# FAL6567e.net
KiCad netlist of a schematic drawn in EAGLE
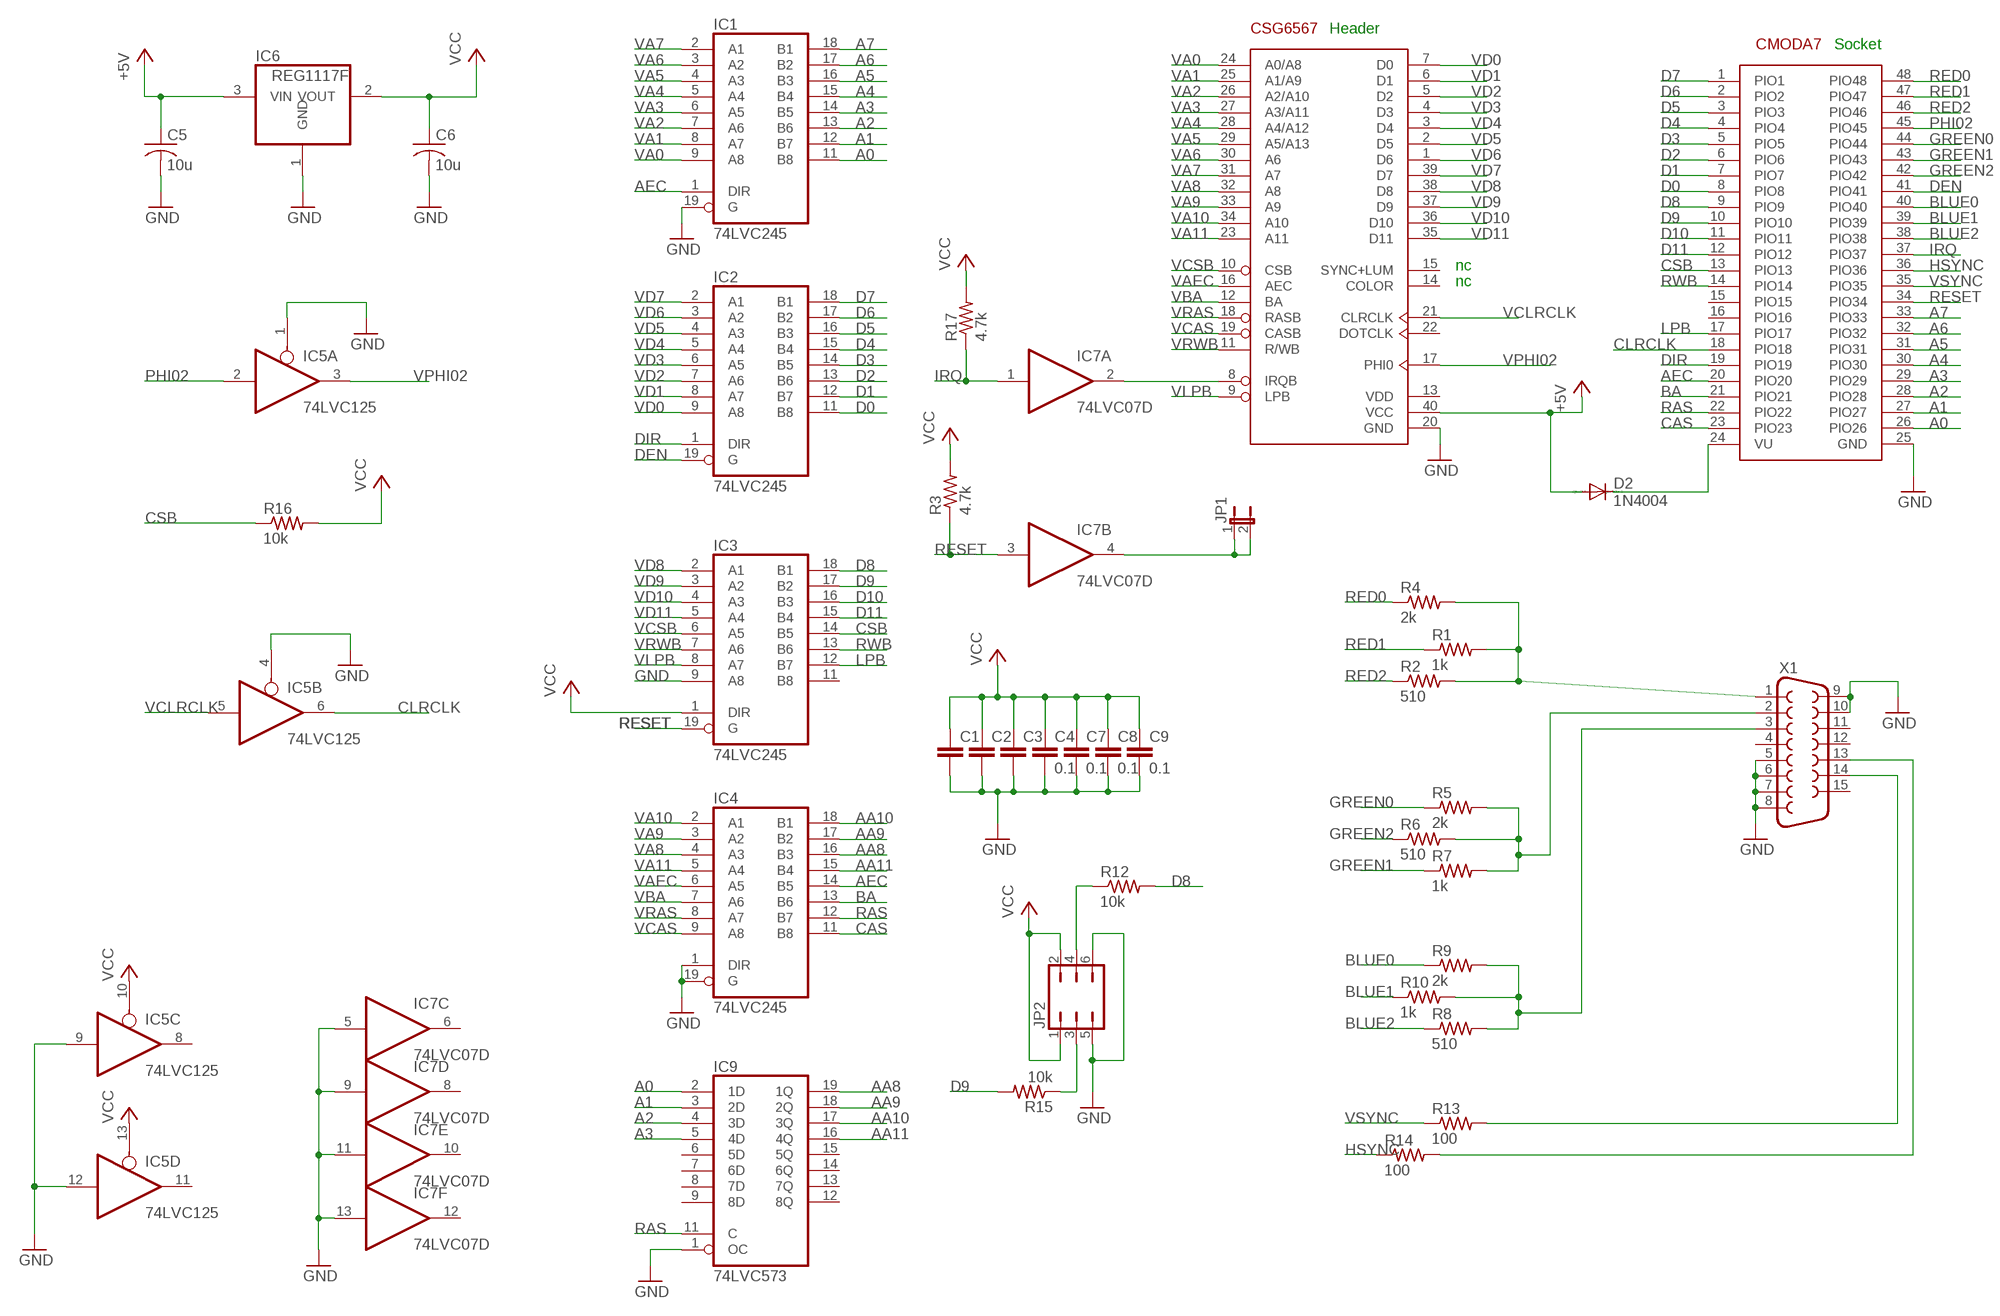
[diagram p0: schematic, sheet 1]

(export (version "E")
  (design (tool "Eeschema 10.0.6"))
  (components
    (comp (ref "C1")
      (value "C-EU050-024X044")
      (footprint "eagle-import:C050-024X044")
      (libsource (lib "eagle-import") (part "C-EU050-024X044"))
    )
    (comp (ref "C2")
      (value "C-EU050-024X044")
      (footprint "eagle-import:C050-024X044")
      (libsource (lib "eagle-import") (part "C-EU050-024X044"))
    )
    (comp (ref "C3")
      (value "C-EU050-024X044")
      (footprint "eagle-import:C050-024X044")
      (libsource (lib "eagle-import") (part "C-EU050-024X044"))
    )
    (comp (ref "C4")
      (value "0.1")
      (footprint "eagle-import:C050-024X044")
      (libsource (lib "eagle-import") (part "C-EU050-024X044"))
    )
    (comp (ref "C5")
      (value "10u")
      (footprint "eagle-import:C1206")
      (libsource (lib "eagle-import") (part "C-USC1206"))
    )
    (comp (ref "C6")
      (value "10u")
      (footprint "eagle-import:C1206")
      (libsource (lib "eagle-import") (part "C-USC1206"))
    )
    (comp (ref "C7")
      (value "0.1")
      (footprint "eagle-import:C050-024X044")
      (libsource (lib "eagle-import") (part "C-EU050-024X044"))
    )
    (comp (ref "C8")
      (value "0.1")
      (footprint "eagle-import:C050-024X044")
      (libsource (lib "eagle-import") (part "C-EU050-024X044"))
    )
    (comp (ref "C9")
      (value "0.1")
      (footprint "eagle-import:C050-024X044")
      (libsource (lib "eagle-import") (part "C-EU050-024X044"))
    )
    (comp (ref "D2")
      (value "1N4004")
      (footprint "eagle-import:DO41-10")
      (libsource (lib "eagle-import") (part "1N4004"))
    )
    (comp (ref "IC1")
      (value "74LVC245")
      (footprint "eagle-import:SO20W")
      (libsource (lib "eagle-import") (part "74245DWLS"))
    )
    (comp (ref "IC2")
      (value "74LVC245")
      (footprint "eagle-import:SO20W")
      (libsource (lib "eagle-import") (part "74245DWLS"))
    )
    (comp (ref "IC3")
      (value "74LVC245")
      (footprint "eagle-import:SO20W")
      (libsource (lib "eagle-import") (part "74245DWLS"))
    )
    (comp (ref "IC4")
      (value "74LVC245")
      (footprint "eagle-import:SO20W")
      (libsource (lib "eagle-import") (part "74245DWLS"))
    )
    (comp (ref "IC5")
      (value "74LVC125")
      (footprint "eagle-import:SO14")
      (libsource (lib "eagle-import") (part "74125LVC"))
    )
    (comp (ref "IC6")
      (value "REG1117F")
      (footprint "eagle-import:DD-3")
      (fields (field (name "MF") "TEXAS INSTRUMENTS") (field (name "MPN") "REG1117FAKTTT"))
      (libsource (lib "eagle-import") (part "REG1117F"))
    )
    (comp (ref "IC7")
      (value "74LVC07D")
      (footprint "eagle-import:SO14")
      (libsource (lib "eagle-import") (part "7407DLS"))
    )
    (comp (ref "IC9")
      (value "74LVC573")
      (footprint "eagle-import:SO20W")
      (libsource (lib "eagle-import") (part "74573LVC"))
    )
    (comp (ref "JP1")
      (value "JP1E")
      (footprint "eagle-import:JP1")
      (libsource (lib "eagle-import") (part "JP1E"))
    )
    (comp (ref "JP2")
      (value "JP3Q")
      (footprint "eagle-import:JP3Q")
      (libsource (lib "eagle-import") (part "JP3Q"))
    )
    (comp (ref "R1")
      (value "1k")
      (footprint "eagle-import:0204_7")
      (libsource (lib "eagle-import") (part "R-US_0204/7"))
    )
    (comp (ref "R2")
      (value "510")
      (footprint "eagle-import:0204_7")
      (libsource (lib "eagle-import") (part "R-US_0204/7"))
    )
    (comp (ref "R3")
      (value "4.7k")
      (footprint "eagle-import:0204_7")
      (libsource (lib "eagle-import") (part "R-US_0204/7"))
    )
    (comp (ref "R4")
      (value "2k")
      (footprint "eagle-import:0204_7")
      (libsource (lib "eagle-import") (part "R-US_0204/7"))
    )
    (comp (ref "R5")
      (value "2k")
      (footprint "eagle-import:0204_7")
      (libsource (lib "eagle-import") (part "R-US_0204/7"))
    )
    (comp (ref "R6")
      (value "510")
      (footprint "eagle-import:0204_7")
      (libsource (lib "eagle-import") (part "R-US_0204/7"))
    )
    (comp (ref "R7")
      (value "1k")
      (footprint "eagle-import:0204_7")
      (libsource (lib "eagle-import") (part "R-US_0204/7"))
    )
    (comp (ref "R8")
      (value "510")
      (footprint "eagle-import:0204_7")
      (libsource (lib "eagle-import") (part "R-US_0204/7"))
    )
    (comp (ref "R9")
      (value "2k")
      (footprint "eagle-import:0204_7")
      (libsource (lib "eagle-import") (part "R-US_0204/7"))
    )
    (comp (ref "R10")
      (value "1k")
      (footprint "eagle-import:0204_7")
      (libsource (lib "eagle-import") (part "R-US_0204/7"))
    )
    (comp (ref "R12")
      (value "10k")
      (footprint "eagle-import:0204_7")
      (libsource (lib "eagle-import") (part "R-US_0204/7"))
    )
    (comp (ref "R13")
      (value "100")
      (footprint "eagle-import:0204_7")
      (libsource (lib "eagle-import") (part "R-US_0204/7"))
    )
    (comp (ref "R14")
      (value "100")
      (footprint "eagle-import:0204_7")
      (libsource (lib "eagle-import") (part "R-US_0204/7"))
    )
    (comp (ref "R15")
      (value "10k")
      (footprint "eagle-import:0204_7")
      (libsource (lib "eagle-import") (part "R-US_0204/7"))
    )
    (comp (ref "R16")
      (value "10k")
      (footprint "eagle-import:0204_7")
      (libsource (lib "eagle-import") (part "R-US_0204/7"))
    )
    (comp (ref "R17")
      (value "4.7k")
      (footprint "eagle-import:0204_7")
      (libsource (lib "eagle-import") (part "R-US_0204/7"))
    )
    (comp (ref "U$1")
      (value "CSG6567")
      (footprint "eagle-import:DIP-40")
      (libsource (lib "eagle-import") (part "CSG6567"))
    )
    (comp (ref "U$2")
      (value "CMODA7")
      (footprint "eagle-import:DIL48")
      (libsource (lib "eagle-import") (part "CMODA7"))
    )
    (comp (ref "X1")
      (value "F15HDV")
      (footprint "eagle-import:HDF15V")
      (libsource (lib "eagle-import") (part "F15HDV"))
    )
  )
  (nets
    (net (code "1") (name "+5V") (class "Default")
      (node (ref "C5") (pin "1") (pinfunction "1_1") (pintype "passive"))
      (node (ref "D2") (pin "A") (pinfunction "A_A") (pintype "passive"))
      (node (ref "IC6") (pin "3") (pinfunction "VIN_3") (pintype "input"))
      (node (ref "U$1") (pin "40") (pinfunction "VCC_40") (pintype "power_in"))
    )
    (net (code "2") (name "/A0") (class "Default")
      (node (ref "IC1") (pin "11") (pinfunction "B8_11") (pintype "bidirectional"))
      (node (ref "IC9") (pin "2") (pinfunction "1D_2") (pintype "input"))
      (node (ref "U$2") (pin "26") (pinfunction "PIO26_26") (pintype "bidirectional"))
    )
    (net (code "3") (name "/A1") (class "Default")
      (node (ref "IC1") (pin "12") (pinfunction "B7_12") (pintype "bidirectional"))
      (node (ref "IC9") (pin "3") (pinfunction "2D_3") (pintype "input"))
      (node (ref "U$2") (pin "27") (pinfunction "PIO27_27") (pintype "bidirectional"))
    )
    (net (code "4") (name "/A2") (class "Default")
      (node (ref "IC1") (pin "13") (pinfunction "B6_13") (pintype "bidirectional"))
      (node (ref "IC9") (pin "4") (pinfunction "3D_4") (pintype "input"))
      (node (ref "U$2") (pin "28") (pinfunction "PIO28_28") (pintype "bidirectional"))
    )
    (net (code "5") (name "/A3") (class "Default")
      (node (ref "IC1") (pin "14") (pinfunction "B5_14") (pintype "bidirectional"))
      (node (ref "IC9") (pin "5") (pinfunction "4D_5") (pintype "input"))
      (node (ref "U$2") (pin "29") (pinfunction "PIO29_29") (pintype "bidirectional"))
    )
    (net (code "6") (name "/A4") (class "Default")
      (node (ref "IC1") (pin "15") (pinfunction "B4_15") (pintype "bidirectional"))
      (node (ref "U$2") (pin "30") (pinfunction "PIO30_30") (pintype "bidirectional"))
    )
    (net (code "7") (name "/A5") (class "Default")
      (node (ref "IC1") (pin "16") (pinfunction "B3_16") (pintype "bidirectional"))
      (node (ref "U$2") (pin "31") (pinfunction "PIO31_31") (pintype "bidirectional"))
    )
    (net (code "8") (name "/A6") (class "Default")
      (node (ref "IC1") (pin "17") (pinfunction "B2_17") (pintype "bidirectional"))
      (node (ref "U$2") (pin "32") (pinfunction "PIO32_32") (pintype "bidirectional"))
    )
    (net (code "9") (name "/A7") (class "Default")
      (node (ref "IC1") (pin "18") (pinfunction "B1_18") (pintype "bidirectional"))
      (node (ref "U$2") (pin "33") (pinfunction "PIO33_33") (pintype "bidirectional"))
    )
    (net (code "10") (name "/AA8") (class "Default")
      (node (ref "IC4") (pin "16") (pinfunction "B3_16") (pintype "bidirectional"))
      (node (ref "IC9") (pin "19") (pinfunction "1Q_19") (pintype "tri_state"))
    )
    (net (code "11") (name "/AA9") (class "Default")
      (node (ref "IC4") (pin "17") (pinfunction "B2_17") (pintype "bidirectional"))
      (node (ref "IC9") (pin "18") (pinfunction "2Q_18") (pintype "tri_state"))
    )
    (net (code "12") (name "/AA10") (class "Default")
      (node (ref "IC4") (pin "18") (pinfunction "B1_18") (pintype "bidirectional"))
      (node (ref "IC9") (pin "17") (pinfunction "3Q_17") (pintype "tri_state"))
    )
    (net (code "13") (name "/AA11") (class "Default")
      (node (ref "IC4") (pin "15") (pinfunction "B4_15") (pintype "bidirectional"))
      (node (ref "IC9") (pin "16") (pinfunction "4Q_16") (pintype "tri_state"))
    )
    (net (code "14") (name "/AEC") (class "Default")
      (node (ref "IC1") (pin "1") (pinfunction "DIR_1") (pintype "input"))
      (node (ref "IC4") (pin "14") (pinfunction "B5_14") (pintype "bidirectional"))
      (node (ref "U$2") (pin "20") (pinfunction "PIO20_20") (pintype "bidirectional"))
    )
    (net (code "15") (name "/BA") (class "Default")
      (node (ref "IC4") (pin "13") (pinfunction "B6_13") (pintype "bidirectional"))
      (node (ref "U$2") (pin "21") (pinfunction "PIO21_21") (pintype "bidirectional"))
    )
    (net (code "16") (name "/BLUE0") (class "Default")
      (node (ref "R9") (pin "1") (pinfunction "1_1") (pintype "passive"))
      (node (ref "U$2") (pin "40") (pinfunction "PIO40_40") (pintype "bidirectional"))
    )
    (net (code "17") (name "/BLUE1") (class "Default")
      (node (ref "R10") (pin "1") (pinfunction "1_1") (pintype "passive"))
      (node (ref "U$2") (pin "39") (pinfunction "PIO39_39") (pintype "bidirectional"))
    )
    (net (code "18") (name "/BLUE2") (class "Default")
      (node (ref "R8") (pin "1") (pinfunction "1_1") (pintype "passive"))
      (node (ref "U$2") (pin "38") (pinfunction "PIO38_38") (pintype "bidirectional"))
    )
    (net (code "19") (name "/CAS") (class "Default")
      (node (ref "IC4") (pin "11") (pinfunction "B8_11") (pintype "bidirectional"))
      (node (ref "U$2") (pin "23") (pinfunction "PIO23_23") (pintype "bidirectional"))
    )
    (net (code "20") (name "/CLRCLK") (class "Default")
      (node (ref "IC5") (pin "6") (pinfunction "O_6") (pintype "tri_state"))
      (node (ref "U$2") (pin "18") (pinfunction "PIO18_18") (pintype "bidirectional"))
    )
    (net (code "21") (name "/CSB") (class "Default")
      (node (ref "IC3") (pin "14") (pinfunction "B5_14") (pintype "bidirectional"))
      (node (ref "R16") (pin "1") (pinfunction "1_1") (pintype "passive"))
      (node (ref "U$2") (pin "13") (pinfunction "PIO13_13") (pintype "bidirectional"))
    )
    (net (code "22") (name "/D0") (class "Default")
      (node (ref "IC2") (pin "11") (pinfunction "B8_11") (pintype "bidirectional"))
      (node (ref "U$2") (pin "8") (pinfunction "PIO8_8") (pintype "bidirectional"))
    )
    (net (code "23") (name "/D1") (class "Default")
      (node (ref "IC2") (pin "12") (pinfunction "B7_12") (pintype "bidirectional"))
      (node (ref "U$2") (pin "7") (pinfunction "PIO7_7") (pintype "bidirectional"))
    )
    (net (code "24") (name "/D2") (class "Default")
      (node (ref "IC2") (pin "13") (pinfunction "B6_13") (pintype "bidirectional"))
      (node (ref "U$2") (pin "6") (pinfunction "PIO6_6") (pintype "bidirectional"))
    )
    (net (code "25") (name "/D3") (class "Default")
      (node (ref "IC2") (pin "14") (pinfunction "B5_14") (pintype "bidirectional"))
      (node (ref "U$2") (pin "5") (pinfunction "PIO5_5") (pintype "bidirectional"))
    )
    (net (code "26") (name "/D4") (class "Default")
      (node (ref "IC2") (pin "15") (pinfunction "B4_15") (pintype "bidirectional"))
      (node (ref "U$2") (pin "4") (pinfunction "PIO4_4") (pintype "bidirectional"))
    )
    (net (code "27") (name "/D5") (class "Default")
      (node (ref "IC2") (pin "16") (pinfunction "B3_16") (pintype "bidirectional"))
      (node (ref "U$2") (pin "3") (pinfunction "PIO3_3") (pintype "bidirectional"))
    )
    (net (code "28") (name "/D6") (class "Default")
      (node (ref "IC2") (pin "17") (pinfunction "B2_17") (pintype "bidirectional"))
      (node (ref "U$2") (pin "2") (pinfunction "PIO2_2") (pintype "bidirectional"))
    )
    (net (code "29") (name "/D7") (class "Default")
      (node (ref "IC2") (pin "18") (pinfunction "B1_18") (pintype "bidirectional"))
      (node (ref "U$2") (pin "1") (pinfunction "PIO1_1") (pintype "bidirectional"))
    )
    (net (code "30") (name "/D8") (class "Default")
      (node (ref "IC3") (pin "18") (pinfunction "B1_18") (pintype "bidirectional"))
      (node (ref "R12") (pin "2") (pinfunction "2_2") (pintype "passive"))
      (node (ref "U$2") (pin "9") (pinfunction "PIO9_9") (pintype "bidirectional"))
    )
    (net (code "31") (name "/D9") (class "Default")
      (node (ref "IC3") (pin "17") (pinfunction "B2_17") (pintype "bidirectional"))
      (node (ref "R15") (pin "2") (pinfunction "2_2") (pintype "passive"))
      (node (ref "U$2") (pin "10") (pinfunction "PIO10_10") (pintype "bidirectional"))
    )
    (net (code "32") (name "/D10") (class "Default")
      (node (ref "IC3") (pin "16") (pinfunction "B3_16") (pintype "bidirectional"))
      (node (ref "U$2") (pin "11") (pinfunction "PIO11_11") (pintype "bidirectional"))
    )
    (net (code "33") (name "/D11") (class "Default")
      (node (ref "IC3") (pin "15") (pinfunction "B4_15") (pintype "bidirectional"))
      (node (ref "U$2") (pin "12") (pinfunction "PIO12_12") (pintype "bidirectional"))
    )
    (net (code "34") (name "/DEN") (class "Default")
      (node (ref "IC2") (pin "19") (pinfunction "G_19") (pintype "input"))
      (node (ref "U$2") (pin "41") (pinfunction "PIO41_41") (pintype "bidirectional"))
    )
    (net (code "35") (name "/DIR") (class "Default")
      (node (ref "IC2") (pin "1") (pinfunction "DIR_1") (pintype "input"))
      (node (ref "U$2") (pin "19") (pinfunction "PIO19_19") (pintype "bidirectional"))
    )
    (net (code "36") (name "/GREEN0") (class "Default")
      (node (ref "R5") (pin "1") (pinfunction "1_1") (pintype "passive"))
      (node (ref "U$2") (pin "44") (pinfunction "PIO44_44") (pintype "bidirectional"))
    )
    (net (code "37") (name "/GREEN1") (class "Default")
      (node (ref "R7") (pin "1") (pinfunction "1_1") (pintype "passive"))
      (node (ref "U$2") (pin "43") (pinfunction "PIO43_43") (pintype "bidirectional"))
    )
    (net (code "38") (name "/GREEN2") (class "Default")
      (node (ref "R6") (pin "1") (pinfunction "1_1") (pintype "passive"))
      (node (ref "U$2") (pin "42") (pinfunction "PIO42_42") (pintype "bidirectional"))
    )
    (net (code "39") (name "/HSYNC") (class "Default")
      (node (ref "R14") (pin "1") (pinfunction "1_1") (pintype "passive"))
      (node (ref "U$2") (pin "36") (pinfunction "PIO36_36") (pintype "bidirectional"))
    )
    (net (code "40") (name "/IRQ") (class "Default")
      (node (ref "IC7") (pin "1") (pinfunction "I_1") (pintype "input"))
      (node (ref "R17") (pin "1") (pinfunction "1_1") (pintype "passive"))
      (node (ref "U$2") (pin "37") (pinfunction "PIO37_37") (pintype "bidirectional"))
    )
    (net (code "41") (name "/LPB") (class "Default")
      (node (ref "IC3") (pin "12") (pinfunction "B7_12") (pintype "bidirectional"))
      (node (ref "U$2") (pin "17") (pinfunction "PIO17_17") (pintype "bidirectional"))
    )
    (net (code "42") (name "/PHI02") (class "Default")
      (node (ref "IC5") (pin "2") (pinfunction "I_2") (pintype "input"))
      (node (ref "U$2") (pin "45") (pinfunction "PIO45_45") (pintype "bidirectional"))
    )
    (net (code "43") (name "/RAS") (class "Default")
      (node (ref "IC4") (pin "12") (pinfunction "B7_12") (pintype "bidirectional"))
      (node (ref "IC9") (pin "11") (pinfunction "C_11") (pintype "input"))
      (node (ref "U$2") (pin "22") (pinfunction "PIO22_22") (pintype "bidirectional"))
    )
    (net (code "44") (name "/RED0") (class "Default")
      (node (ref "R4") (pin "1") (pinfunction "1_1") (pintype "passive"))
      (node (ref "U$2") (pin "48") (pinfunction "PIO48_48") (pintype "bidirectional"))
    )
    (net (code "45") (name "/RED1") (class "Default")
      (node (ref "R1") (pin "1") (pinfunction "1_1") (pintype "passive"))
      (node (ref "U$2") (pin "47") (pinfunction "PIO47_47") (pintype "bidirectional"))
    )
    (net (code "46") (name "/RED2") (class "Default")
      (node (ref "R2") (pin "1") (pinfunction "1_1") (pintype "passive"))
      (node (ref "U$2") (pin "46") (pinfunction "PIO46_46") (pintype "bidirectional"))
    )
    (net (code "47") (name "/RESET") (class "Default")
      (node (ref "IC3") (pin "19") (pinfunction "G_19") (pintype "input"))
      (node (ref "IC7") (pin "3") (pinfunction "I_3") (pintype "input"))
      (node (ref "R3") (pin "1") (pinfunction "1_1") (pintype "passive"))
      (node (ref "U$2") (pin "34") (pinfunction "PIO34_34") (pintype "bidirectional"))
    )
    (net (code "48") (name "/RWB") (class "Default")
      (node (ref "IC3") (pin "13") (pinfunction "B6_13") (pintype "bidirectional"))
      (node (ref "U$2") (pin "14") (pinfunction "PIO14_14") (pintype "bidirectional"))
    )
    (net (code "49") (name "/VA0") (class "Default")
      (node (ref "IC1") (pin "9") (pinfunction "A8_9") (pintype "bidirectional"))
      (node (ref "U$1") (pin "24") (pinfunction "A0/A8_24") (pintype "bidirectional"))
    )
    (net (code "50") (name "/VA1") (class "Default")
      (node (ref "IC1") (pin "8") (pinfunction "A7_8") (pintype "bidirectional"))
      (node (ref "U$1") (pin "25") (pinfunction "A1/A9_25") (pintype "bidirectional"))
    )
    (net (code "51") (name "/VA2") (class "Default")
      (node (ref "IC1") (pin "7") (pinfunction "A6_7") (pintype "bidirectional"))
      (node (ref "U$1") (pin "26") (pinfunction "A2/A10_26") (pintype "bidirectional"))
    )
    (net (code "52") (name "/VA3") (class "Default")
      (node (ref "IC1") (pin "6") (pinfunction "A5_6") (pintype "bidirectional"))
      (node (ref "U$1") (pin "27") (pinfunction "A3/A11_27") (pintype "bidirectional"))
    )
    (net (code "53") (name "/VA4") (class "Default")
      (node (ref "IC1") (pin "5") (pinfunction "A4_5") (pintype "bidirectional"))
      (node (ref "U$1") (pin "28") (pinfunction "A4/A12_28") (pintype "bidirectional"))
    )
    (net (code "54") (name "/VA5") (class "Default")
      (node (ref "IC1") (pin "4") (pinfunction "A3_4") (pintype "bidirectional"))
      (node (ref "U$1") (pin "29") (pinfunction "A5/A13_29") (pintype "bidirectional"))
    )
    (net (code "55") (name "/VA6") (class "Default")
      (node (ref "IC1") (pin "3") (pinfunction "A2_3") (pintype "bidirectional"))
      (node (ref "U$1") (pin "30") (pinfunction "A6_30") (pintype "bidirectional"))
    )
    (net (code "56") (name "/VA7") (class "Default")
      (node (ref "IC1") (pin "2") (pinfunction "A1_2") (pintype "bidirectional"))
      (node (ref "U$1") (pin "31") (pinfunction "A7_31") (pintype "bidirectional"))
    )
    (net (code "57") (name "/VA8") (class "Default")
      (node (ref "IC4") (pin "4") (pinfunction "A3_4") (pintype "bidirectional"))
      (node (ref "U$1") (pin "32") (pinfunction "A8_32") (pintype "output"))
    )
    (net (code "58") (name "/VA9") (class "Default")
      (node (ref "IC4") (pin "3") (pinfunction "A2_3") (pintype "bidirectional"))
      (node (ref "U$1") (pin "33") (pinfunction "A9_33") (pintype "output"))
    )
    (net (code "59") (name "/VA10") (class "Default")
      (node (ref "IC4") (pin "2") (pinfunction "A1_2") (pintype "bidirectional"))
      (node (ref "U$1") (pin "34") (pinfunction "A10_34") (pintype "output"))
    )
    (net (code "60") (name "/VA11") (class "Default")
      (node (ref "IC4") (pin "5") (pinfunction "A4_5") (pintype "bidirectional"))
      (node (ref "U$1") (pin "23") (pinfunction "A11_23") (pintype "output"))
    )
    (net (code "61") (name "/VAEC") (class "Default")
      (node (ref "IC4") (pin "6") (pinfunction "A5_6") (pintype "bidirectional"))
      (node (ref "U$1") (pin "16") (pinfunction "AEC_16") (pintype "output"))
    )
    (net (code "62") (name "/VBA") (class "Default")
      (node (ref "IC4") (pin "7") (pinfunction "A6_7") (pintype "bidirectional"))
      (node (ref "U$1") (pin "12") (pinfunction "BA_12") (pintype "output"))
    )
    (net (code "63") (name "/VCAS") (class "Default")
      (node (ref "IC4") (pin "9") (pinfunction "A8_9") (pintype "bidirectional"))
      (node (ref "U$1") (pin "19") (pinfunction "CASB_19") (pintype "output"))
    )
    (net (code "64") (name "/VCLRCLK") (class "Default")
      (node (ref "IC5") (pin "5") (pinfunction "I_5") (pintype "input"))
      (node (ref "U$1") (pin "21") (pinfunction "CLRCLK_21") (pintype "input"))
    )
    (net (code "65") (name "/VCSB") (class "Default")
      (node (ref "IC3") (pin "6") (pinfunction "A5_6") (pintype "bidirectional"))
      (node (ref "U$1") (pin "10") (pinfunction "CSB_10") (pintype "input"))
    )
    (net (code "66") (name "/VD0") (class "Default")
      (node (ref "IC2") (pin "9") (pinfunction "A8_9") (pintype "bidirectional"))
      (node (ref "U$1") (pin "7") (pinfunction "D0_7") (pintype "bidirectional"))
    )
    (net (code "67") (name "/VD1") (class "Default")
      (node (ref "IC2") (pin "8") (pinfunction "A7_8") (pintype "bidirectional"))
      (node (ref "U$1") (pin "6") (pinfunction "D1_6") (pintype "bidirectional"))
    )
    (net (code "68") (name "/VD2") (class "Default")
      (node (ref "IC2") (pin "7") (pinfunction "A6_7") (pintype "bidirectional"))
      (node (ref "U$1") (pin "5") (pinfunction "D2_5") (pintype "bidirectional"))
    )
    (net (code "69") (name "/VD3") (class "Default")
      (node (ref "IC2") (pin "6") (pinfunction "A5_6") (pintype "bidirectional"))
      (node (ref "U$1") (pin "4") (pinfunction "D3_4") (pintype "bidirectional"))
    )
    (net (code "70") (name "/VD4") (class "Default")
      (node (ref "IC2") (pin "5") (pinfunction "A4_5") (pintype "bidirectional"))
      (node (ref "U$1") (pin "3") (pinfunction "D4_3") (pintype "bidirectional"))
    )
    (net (code "71") (name "/VD5") (class "Default")
      (node (ref "IC2") (pin "4") (pinfunction "A3_4") (pintype "bidirectional"))
      (node (ref "U$1") (pin "2") (pinfunction "D5_2") (pintype "bidirectional"))
    )
    (net (code "72") (name "/VD6") (class "Default")
      (node (ref "IC2") (pin "3") (pinfunction "A2_3") (pintype "bidirectional"))
      (node (ref "U$1") (pin "1") (pinfunction "D6_1") (pintype "bidirectional"))
    )
    (net (code "73") (name "/VD7") (class "Default")
      (node (ref "IC2") (pin "2") (pinfunction "A1_2") (pintype "bidirectional"))
      (node (ref "U$1") (pin "39") (pinfunction "D7_39") (pintype "bidirectional"))
    )
    (net (code "74") (name "/VD8") (class "Default")
      (node (ref "IC3") (pin "2") (pinfunction "A1_2") (pintype "bidirectional"))
      (node (ref "U$1") (pin "38") (pinfunction "D8_38") (pintype "input"))
    )
    (net (code "75") (name "/VD9") (class "Default")
      (node (ref "IC3") (pin "3") (pinfunction "A2_3") (pintype "bidirectional"))
      (node (ref "U$1") (pin "37") (pinfunction "D9_37") (pintype "input"))
    )
    (net (code "76") (name "/VD10") (class "Default")
      (node (ref "IC3") (pin "4") (pinfunction "A3_4") (pintype "bidirectional"))
      (node (ref "U$1") (pin "36") (pinfunction "D10_36") (pintype "input"))
    )
    (net (code "77") (name "/VD11") (class "Default")
      (node (ref "IC3") (pin "5") (pinfunction "A4_5") (pintype "bidirectional"))
      (node (ref "U$1") (pin "35") (pinfunction "D11_35") (pintype "input"))
    )
    (net (code "78") (name "/VDD") (class "Default")
      (node (ref "U$1") (pin "13") (pinfunction "VDD_13") (pintype "power_in"))
    )
    (net (code "79") (name "/VLPB") (class "Default")
      (node (ref "IC3") (pin "8") (pinfunction "A7_8") (pintype "bidirectional"))
      (node (ref "U$1") (pin "9") (pinfunction "LPB_9") (pintype "input"))
    )
    (net (code "80") (name "/VPHI02") (class "Default")
      (node (ref "IC5") (pin "3") (pinfunction "O_3") (pintype "tri_state"))
      (node (ref "U$1") (pin "17") (pinfunction "PHI0_17") (pintype "output"))
    )
    (net (code "81") (name "/VRAS") (class "Default")
      (node (ref "IC4") (pin "8") (pinfunction "A7_8") (pintype "bidirectional"))
      (node (ref "U$1") (pin "18") (pinfunction "RASB_18") (pintype "output"))
    )
    (net (code "82") (name "/VRWB") (class "Default")
      (node (ref "IC3") (pin "7") (pinfunction "A6_7") (pintype "bidirectional"))
      (node (ref "U$1") (pin "11") (pinfunction "R/WB_11") (pintype "input"))
    )
    (net (code "83") (name "/VSYNC") (class "Default")
      (node (ref "R13") (pin "1") (pinfunction "1_1") (pintype "passive"))
      (node (ref "U$2") (pin "35") (pinfunction "PIO35_35") (pintype "bidirectional"))
    )
    (net (code "84") (name "GND") (class "Default")
      (node (ref "C1") (pin "2") (pinfunction "2_2") (pintype "passive"))
      (node (ref "C2") (pin "2") (pinfunction "2_2") (pintype "passive"))
      (node (ref "C3") (pin "2") (pinfunction "2_2") (pintype "passive"))
      (node (ref "C4") (pin "2") (pinfunction "2_2") (pintype "passive"))
      (node (ref "C5") (pin "2") (pinfunction "2_2") (pintype "passive"))
      (node (ref "C6") (pin "2") (pinfunction "2_2") (pintype "passive"))
      (node (ref "C7") (pin "2") (pinfunction "2_2") (pintype "passive"))
      (node (ref "C8") (pin "2") (pinfunction "2_2") (pintype "passive"))
      (node (ref "C9") (pin "2") (pinfunction "2_2") (pintype "passive"))
      (node (ref "IC1") (pin "19") (pinfunction "G_19") (pintype "input"))
      (node (ref "IC3") (pin "9") (pinfunction "A8_9") (pintype "bidirectional"))
      (node (ref "IC4") (pin "1") (pinfunction "DIR_1") (pintype "input"))
      (node (ref "IC4") (pin "19") (pinfunction "G_19") (pintype "input"))
      (node (ref "IC5") (pin "1") (pinfunction "OE_1") (pintype "input"))
      (node (ref "IC5") (pin "12") (pinfunction "I_12") (pintype "input"))
      (node (ref "IC5") (pin "4") (pinfunction "OE_4") (pintype "input"))
      (node (ref "IC5") (pin "9") (pinfunction "I_9") (pintype "input"))
      (node (ref "IC6") (pin "1") (pinfunction "GND_1") (pintype "power_in"))
      (node (ref "IC7") (pin "11") (pinfunction "I_11") (pintype "input"))
      (node (ref "IC7") (pin "13") (pinfunction "I_13") (pintype "input"))
      (node (ref "IC7") (pin "5") (pinfunction "I_5") (pintype "input"))
      (node (ref "IC7") (pin "9") (pinfunction "I_9") (pintype "input"))
      (node (ref "IC9") (pin "1") (pinfunction "OC_1") (pintype "input"))
      (node (ref "JP2") (pin "5") (pinfunction "5_5") (pintype "passive"))
      (node (ref "JP2") (pin "6") (pinfunction "6_6") (pintype "passive"))
      (node (ref "U$1") (pin "20") (pinfunction "GND_20") (pintype "power_in"))
      (node (ref "U$2") (pin "25") (pinfunction "GND_25") (pintype "power_in"))
      (node (ref "X1") (pin "10") (pinfunction "10_10") (pintype "passive"))
      (node (ref "X1") (pin "5") (pinfunction "5_5") (pintype "passive"))
      (node (ref "X1") (pin "6") (pinfunction "6_6") (pintype "passive"))
      (node (ref "X1") (pin "7") (pinfunction "7_7") (pintype "passive"))
      (node (ref "X1") (pin "8") (pinfunction "8_8") (pintype "passive"))
      (node (ref "X1") (pin "9") (pinfunction "9_9") (pintype "passive"))
    )
    (net (code "85") (name "Net-(IC7A-O)") (class "Default")
      (node (ref "IC7") (pin "2") (pinfunction "O_2") (pintype "open_collector"))
      (node (ref "U$1") (pin "8") (pinfunction "IRQB_8") (pintype "open_collector"))
    )
    (net (code "86") (name "Net-(IC7B-O)") (class "Default")
      (node (ref "IC7") (pin "4") (pinfunction "O_4") (pintype "open_collector"))
      (node (ref "JP1") (pin "1") (pinfunction "1_1") (pintype "passive"))
      (node (ref "JP1") (pin "2") (pinfunction "2_2") (pintype "passive"))
    )
    (net (code "87") (name "Net-(JP2-Pad3)") (class "Default")
      (node (ref "JP2") (pin "3") (pinfunction "3_3") (pintype "passive"))
      (node (ref "R15") (pin "1") (pinfunction "1_1") (pintype "passive"))
    )
    (net (code "88") (name "Net-(JP2-Pad4)") (class "Default")
      (node (ref "JP2") (pin "4") (pinfunction "4_4") (pintype "passive"))
      (node (ref "R12") (pin "1") (pinfunction "1_1") (pintype "passive"))
    )
    (net (code "89") (name "Net-(R1-Pad2)") (class "Default")
      (node (ref "R1") (pin "2") (pinfunction "2_2") (pintype "passive"))
      (node (ref "R2") (pin "2") (pinfunction "2_2") (pintype "passive"))
      (node (ref "R4") (pin "2") (pinfunction "2_2") (pintype "passive"))
      (node (ref "X1") (pin "1") (pinfunction "1_1") (pintype "passive"))
    )
    (net (code "90") (name "Net-(R5-Pad2)") (class "Default")
      (node (ref "R5") (pin "2") (pinfunction "2_2") (pintype "passive"))
      (node (ref "R6") (pin "2") (pinfunction "2_2") (pintype "passive"))
      (node (ref "R7") (pin "2") (pinfunction "2_2") (pintype "passive"))
      (node (ref "X1") (pin "2") (pinfunction "2_2") (pintype "passive"))
    )
    (net (code "91") (name "Net-(R10-Pad2)") (class "Default")
      (node (ref "R10") (pin "2") (pinfunction "2_2") (pintype "passive"))
      (node (ref "R8") (pin "2") (pinfunction "2_2") (pintype "passive"))
      (node (ref "R9") (pin "2") (pinfunction "2_2") (pintype "passive"))
      (node (ref "X1") (pin "3") (pinfunction "3_3") (pintype "passive"))
    )
    (net (code "92") (name "Net-(R13-Pad2)") (class "Default")
      (node (ref "R13") (pin "2") (pinfunction "2_2") (pintype "passive"))
      (node (ref "X1") (pin "14") (pinfunction "14_14") (pintype "passive"))
    )
    (net (code "93") (name "Net-(R14-Pad2)") (class "Default")
      (node (ref "R14") (pin "2") (pinfunction "2_2") (pintype "passive"))
      (node (ref "X1") (pin "13") (pinfunction "13_13") (pintype "passive"))
    )
    (net (code "94") (name "Net-(U$2-VU)") (class "Default")
      (node (ref "D2") (pin "C") (pinfunction "C_C") (pintype "passive"))
      (node (ref "U$2") (pin "24") (pinfunction "VU_24") (pintype "power_in"))
    )
    (net (code "95") (name "VCC") (class "Default")
      (node (ref "C1") (pin "1") (pinfunction "1_1") (pintype "passive"))
      (node (ref "C2") (pin "1") (pinfunction "1_1") (pintype "passive"))
      (node (ref "C3") (pin "1") (pinfunction "1_1") (pintype "passive"))
      (node (ref "C4") (pin "1") (pinfunction "1_1") (pintype "passive"))
      (node (ref "C6") (pin "1") (pinfunction "1_1") (pintype "passive"))
      (node (ref "C7") (pin "1") (pinfunction "1_1") (pintype "passive"))
      (node (ref "C8") (pin "1") (pinfunction "1_1") (pintype "passive"))
      (node (ref "C9") (pin "1") (pinfunction "1_1") (pintype "passive"))
      (node (ref "IC3") (pin "1") (pinfunction "DIR_1") (pintype "input"))
      (node (ref "IC5") (pin "10") (pinfunction "OE_10") (pintype "input"))
      (node (ref "IC5") (pin "13") (pinfunction "OE_13") (pintype "input"))
      (node (ref "IC6") (pin "2") (pinfunction "VOUT_2") (pintype "output"))
      (node (ref "JP2") (pin "1") (pinfunction "1_1") (pintype "passive"))
      (node (ref "JP2") (pin "2") (pinfunction "2_2") (pintype "passive"))
      (node (ref "R16") (pin "2") (pinfunction "2_2") (pintype "passive"))
      (node (ref "R17") (pin "2") (pinfunction "2_2") (pintype "passive"))
      (node (ref "R3") (pin "2") (pinfunction "2_2") (pintype "passive"))
    )
    (net (code "96") (name "unconnected-(IC3A-B8-Pad11)") (class "Default")
      (node (ref "IC3") (pin "11") (pinfunction "B8_11") (pintype "bidirectional"))
    )
    (net (code "97") (name "unconnected-(IC5C-O-Pad8)") (class "Default")
      (node (ref "IC5") (pin "8") (pinfunction "O_8") (pintype "tri_state"))
    )
    (net (code "98") (name "unconnected-(IC5D-O-Pad11)") (class "Default")
      (node (ref "IC5") (pin "11") (pinfunction "O_11") (pintype "tri_state"))
    )
    (net (code "99") (name "unconnected-(IC7C-O-Pad6)") (class "Default")
      (node (ref "IC7") (pin "6") (pinfunction "O_6") (pintype "open_collector"))
    )
    (net (code "100") (name "unconnected-(IC7D-O-Pad8)") (class "Default")
      (node (ref "IC7") (pin "8") (pinfunction "O_8") (pintype "open_collector"))
    )
    (net (code "101") (name "unconnected-(IC7E-O-Pad10)") (class "Default")
      (node (ref "IC7") (pin "10") (pinfunction "O_10") (pintype "open_collector"))
    )
    (net (code "102") (name "unconnected-(IC7F-O-Pad12)") (class "Default")
      (node (ref "IC7") (pin "12") (pinfunction "O_12") (pintype "open_collector"))
    )
    (net (code "103") (name "unconnected-(IC9A-5D-Pad6)") (class "Default")
      (node (ref "IC9") (pin "6") (pinfunction "5D_6") (pintype "input"))
    )
    (net (code "104") (name "unconnected-(IC9A-5Q-Pad15)") (class "Default")
      (node (ref "IC9") (pin "15") (pinfunction "5Q_15") (pintype "tri_state"))
    )
    (net (code "105") (name "unconnected-(IC9A-6D-Pad7)") (class "Default")
      (node (ref "IC9") (pin "7") (pinfunction "6D_7") (pintype "input"))
    )
    (net (code "106") (name "unconnected-(IC9A-6Q-Pad14)") (class "Default")
      (node (ref "IC9") (pin "14") (pinfunction "6Q_14") (pintype "tri_state"))
    )
    (net (code "107") (name "unconnected-(IC9A-7D-Pad8)") (class "Default")
      (node (ref "IC9") (pin "8") (pinfunction "7D_8") (pintype "input"))
    )
    (net (code "108") (name "unconnected-(IC9A-7Q-Pad13)") (class "Default")
      (node (ref "IC9") (pin "13") (pinfunction "7Q_13") (pintype "tri_state"))
    )
    (net (code "109") (name "unconnected-(IC9A-8D-Pad9)") (class "Default")
      (node (ref "IC9") (pin "9") (pinfunction "8D_9") (pintype "input"))
    )
    (net (code "110") (name "unconnected-(IC9A-8Q-Pad12)") (class "Default")
      (node (ref "IC9") (pin "12") (pinfunction "8Q_12") (pintype "tri_state"))
    )
    (net (code "111") (name "unconnected-(U$1-COLOR-Pad14)") (class "Default")
      (node (ref "U$1") (pin "14") (pinfunction "COLOR_14") (pintype "output"))
    )
    (net (code "112") (name "unconnected-(U$1-DOTCLK-Pad22)") (class "Default")
      (node (ref "U$1") (pin "22") (pinfunction "DOTCLK_22") (pintype "input"))
    )
    (net (code "113") (name "unconnected-(U$1-SYNC+LUM-Pad15)") (class "Default")
      (node (ref "U$1") (pin "15") (pinfunction "SYNC+LUM_15") (pintype "output"))
    )
    (net (code "114") (name "unconnected-(U$2-PIO15-Pad15)") (class "Default")
      (node (ref "U$2") (pin "15") (pinfunction "PIO15_15") (pintype "bidirectional"))
    )
    (net (code "115") (name "unconnected-(U$2-PIO16-Pad16)") (class "Default")
      (node (ref "U$2") (pin "16") (pinfunction "PIO16_16") (pintype "bidirectional"))
    )
    (net (code "116") (name "unconnected-(X1-Pad4)") (class "Default")
      (node (ref "X1") (pin "4") (pinfunction "4_4") (pintype "passive"))
    )
    (net (code "117") (name "unconnected-(X1-Pad11)") (class "Default")
      (node (ref "X1") (pin "11") (pinfunction "11_11") (pintype "passive"))
    )
    (net (code "118") (name "unconnected-(X1-Pad12)") (class "Default")
      (node (ref "X1") (pin "12") (pinfunction "12_12") (pintype "passive"))
    )
    (net (code "119") (name "unconnected-(X1-Pad15)") (class "Default")
      (node (ref "X1") (pin "15") (pinfunction "15_15") (pintype "passive"))
    )
  )
)
